# Cou_Droit.net
KiCad netlist of a schematic drawn in EasyEDA
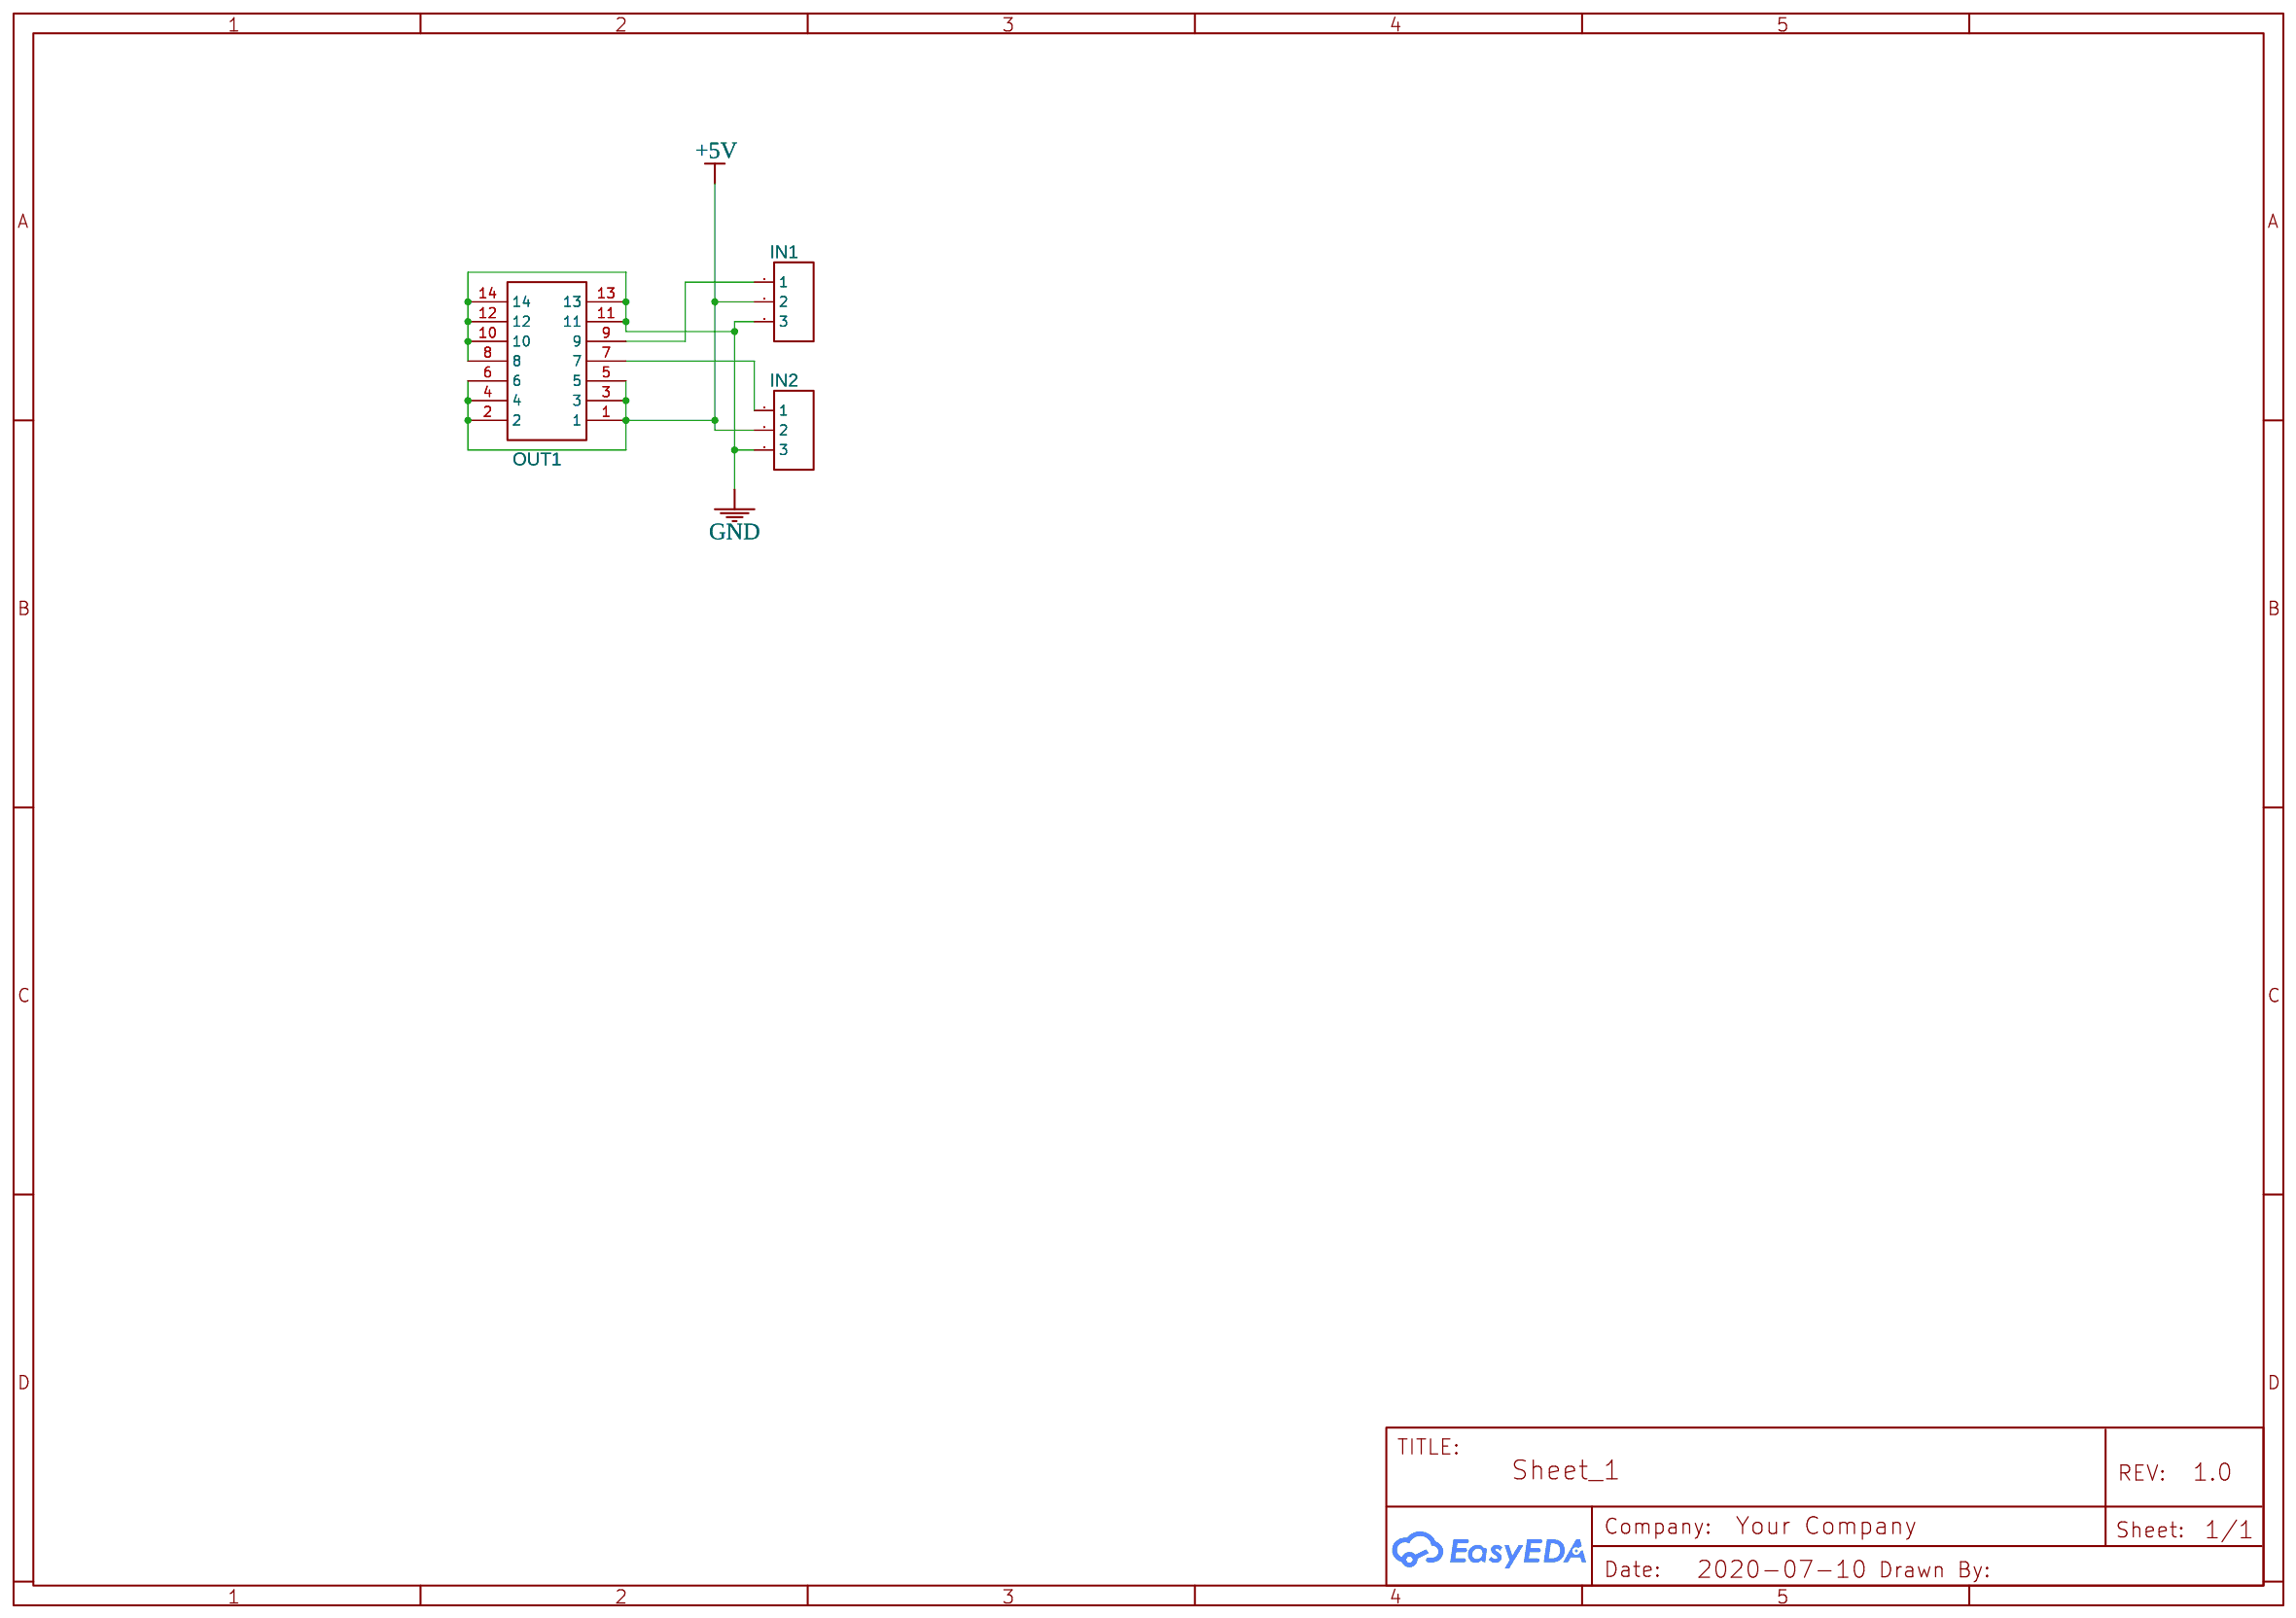
[diagram p0: schematic sheet]

(export (version "E")
  (design (tool "Eeschema 10.0.6"))
  (components
    (comp (ref "IN1")
      (value "1")
      (fields
        (field (name "BOM_Manufacturer Part") "Header2.54mm 1*3P")
        (field (name "BOM_Supplier Part") "C49257")
      )
      (libsource (lib "") (part "Header-Male-2.54_1x3"))
    )
    (comp (ref "IN2")
      (value "1")
      (fields
        (field (name "BOM_Manufacturer Part") "Header2.54mm 1*3P")
        (field (name "BOM_Supplier Part") "C49257")
      )
      (libsource (lib "") (part "Header-Male-2.54_1x3"))
    )
    (comp (ref "OUT1")
      (value "Horn connector/2.0mm2*7P")
      (fields
        (field (name "BOM_Manufacturer Part") "Horn connector/2.0mm2*7P直简牛")
        (field (name "BOM_Supplier Part") "C29428")
      )
      (libsource (lib "") (part "Horn connector/2.0mm2*7P"))
    )
  )
  (nets
    (net (code "1") (name "+5V") (class "Default")
      (node (ref "IN1") (pin "2") (pinfunction "2_2") (pintype "input"))
      (node (ref "IN2") (pin "2") (pinfunction "2_2") (pintype "input"))
      (node (ref "OUT1") (pin "1") (pinfunction "1_1") (pintype "unspecified"))
      (node (ref "OUT1") (pin "2") (pinfunction "2_2") (pintype "unspecified"))
      (node (ref "OUT1") (pin "3") (pinfunction "3_3") (pintype "unspecified"))
      (node (ref "OUT1") (pin "4") (pinfunction "4_4") (pintype "unspecified"))
      (node (ref "OUT1") (pin "5") (pinfunction "5_5") (pintype "unspecified"))
      (node (ref "OUT1") (pin "6") (pinfunction "6_6") (pintype "unspecified"))
    )
    (net (code "2") (name "GND") (class "Default")
      (node (ref "IN1") (pin "3") (pinfunction "3_3") (pintype "input"))
      (node (ref "IN2") (pin "3") (pinfunction "3_3") (pintype "input"))
      (node (ref "OUT1") (pin "10") (pinfunction "10_10") (pintype "unspecified"))
      (node (ref "OUT1") (pin "11") (pinfunction "11_11") (pintype "unspecified"))
      (node (ref "OUT1") (pin "12") (pinfunction "12_12") (pintype "unspecified"))
      (node (ref "OUT1") (pin "13") (pinfunction "13_13") (pintype "unspecified"))
      (node (ref "OUT1") (pin "14") (pinfunction "14_14") (pintype "unspecified"))
      (node (ref "OUT1") (pin "8") (pinfunction "8_8") (pintype "unspecified"))
    )
    (net (code "3") (name "Net-(IN1-Pad1)") (class "Default")
      (node (ref "IN1") (pin "1") (pinfunction "1_1") (pintype "input"))
      (node (ref "OUT1") (pin "9") (pinfunction "9_9") (pintype "unspecified"))
    )
    (net (code "4") (name "Net-(IN2-Pad1)") (class "Default")
      (node (ref "IN2") (pin "1") (pinfunction "1_1") (pintype "input"))
      (node (ref "OUT1") (pin "7") (pinfunction "7_7") (pintype "unspecified"))
    )
  )
)
